# ESP32-S3-DevKit-C1.net
KiCad netlist of a schematic drawn in EasyEDA Pro
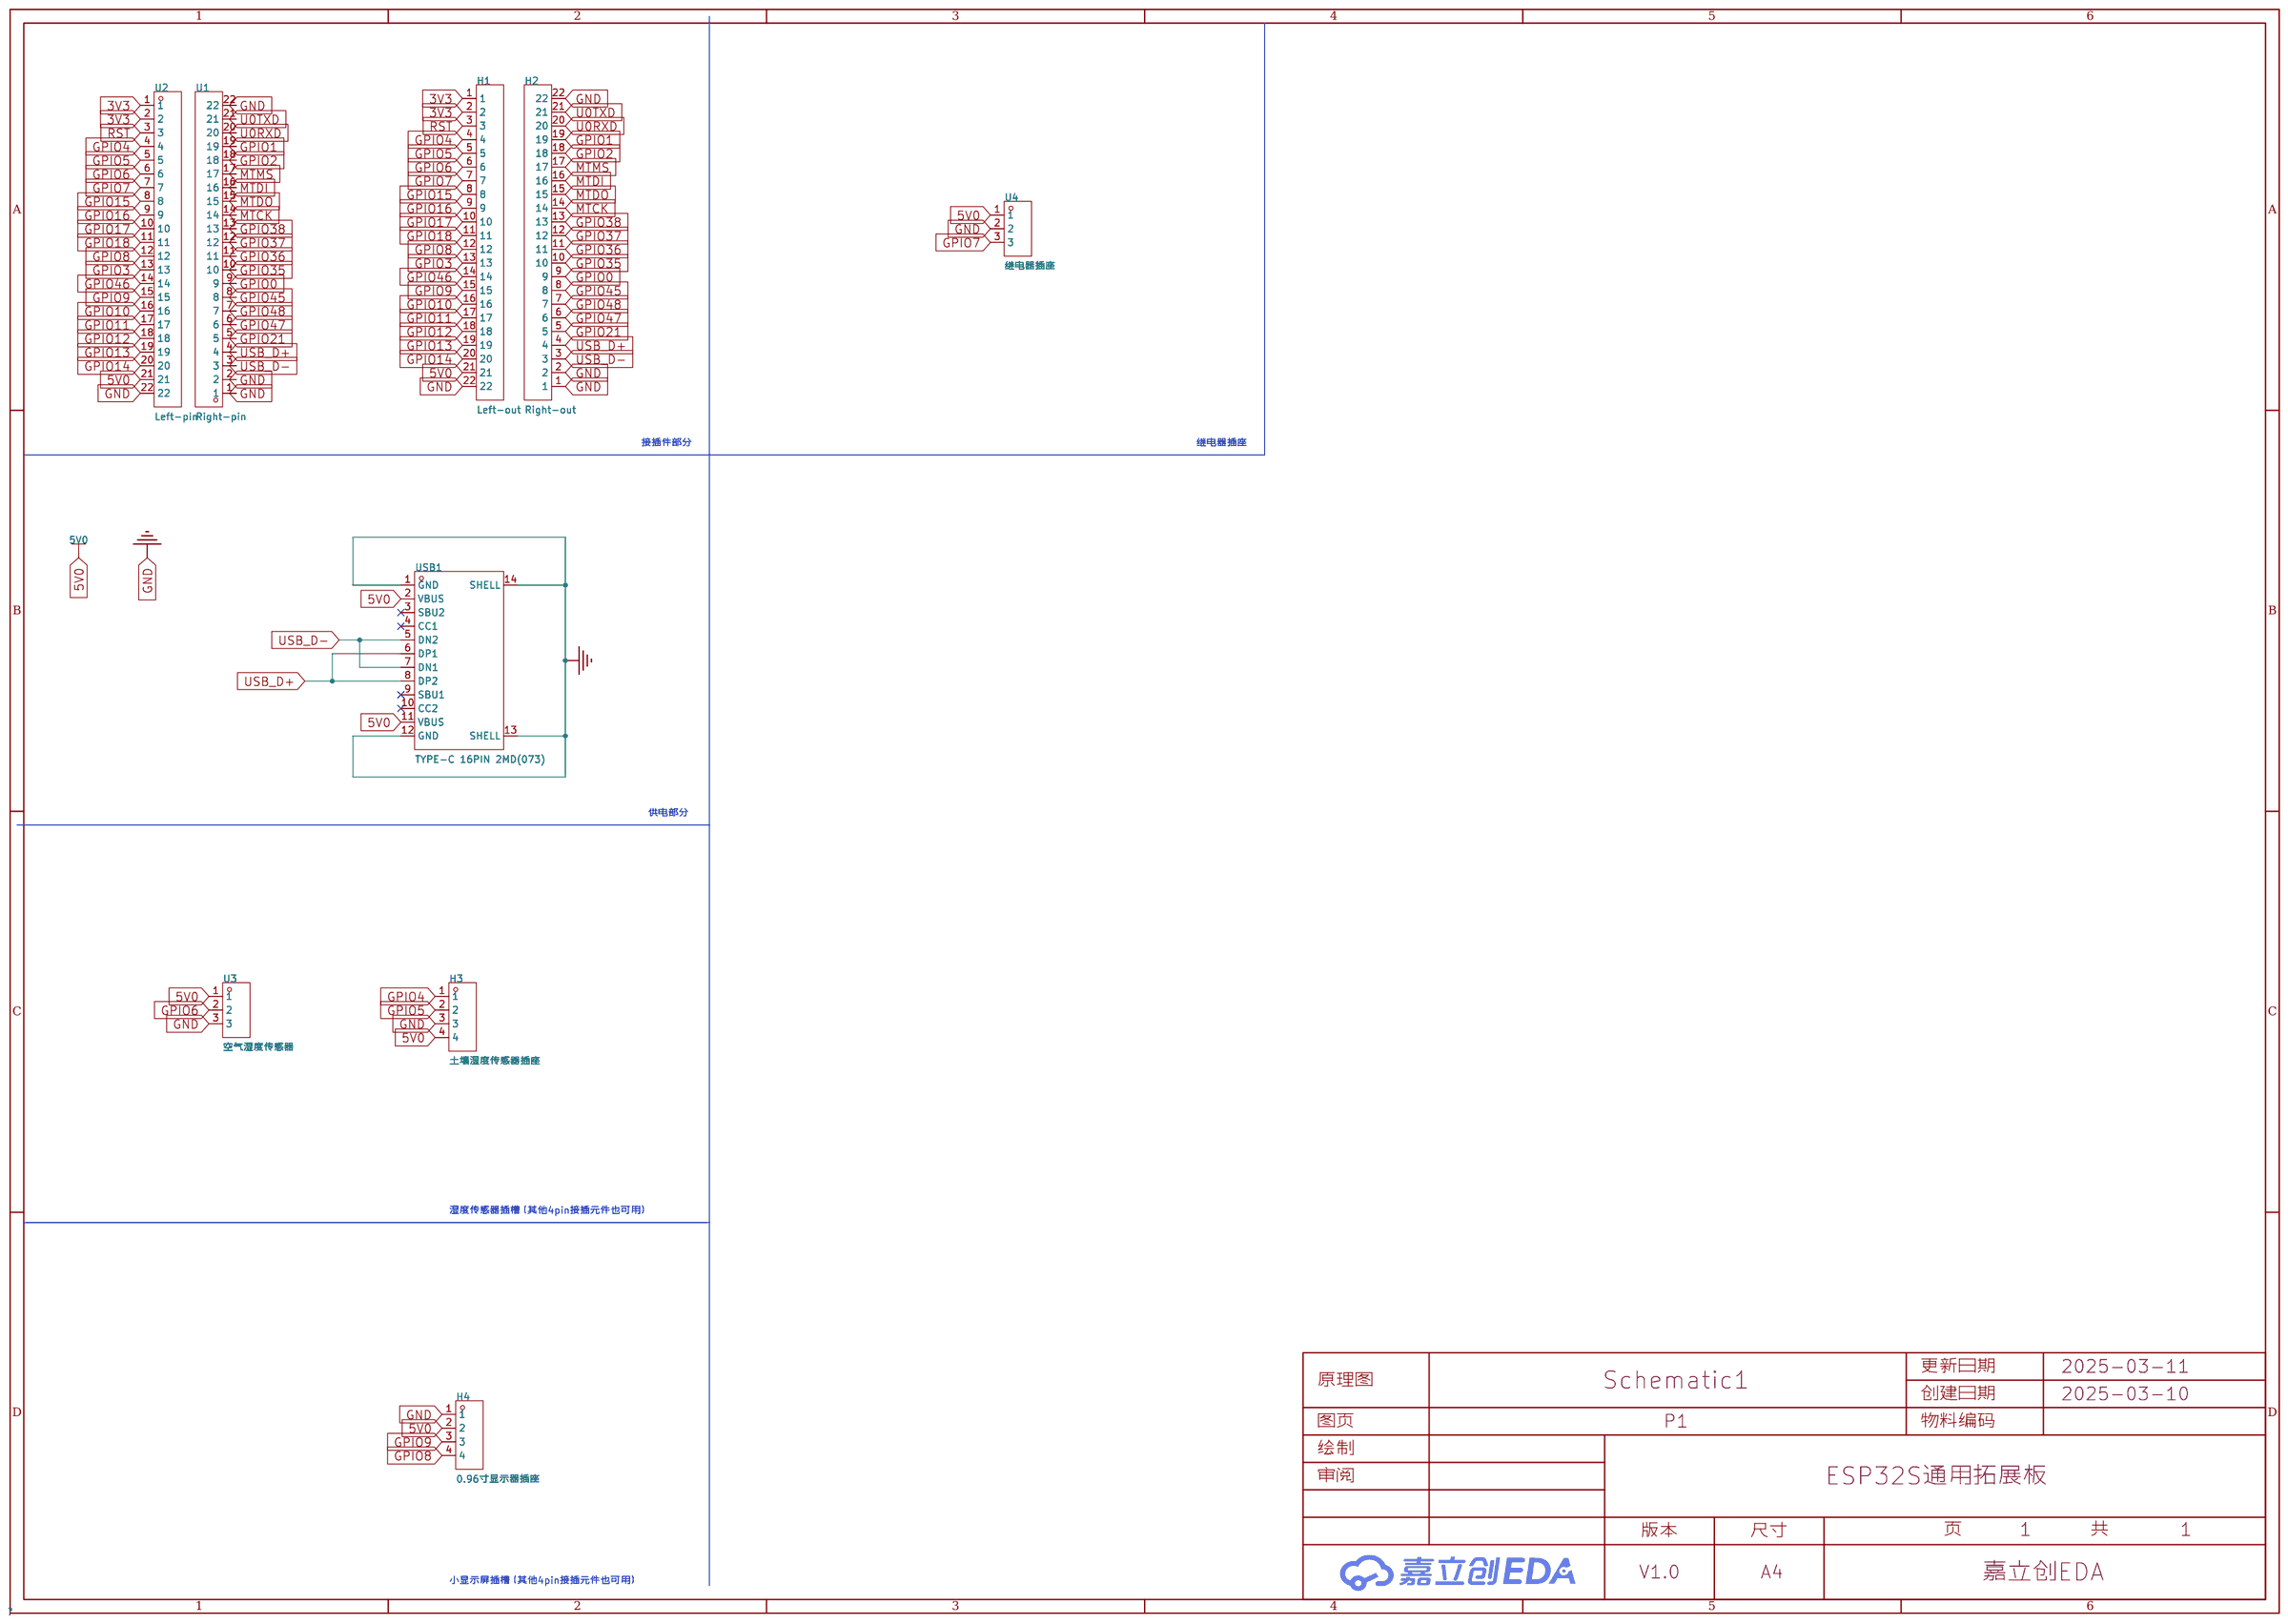
[diagram p0: schematic sheet]

(export (version "E")
  (design (tool "Eeschema 10.0.6"))
  (components
    (comp (ref "H1")
      (value "Left-out")
      (footprint "easyedapro:HDR-TH_22P-P2.54-V-M")
      (fields (field (name "Manufacturer") "XKB Connection(中国星坤)"))
      (libsource (lib "easyedapro") (part "X6511WV-22H-C30D60"))
    )
    (comp (ref "H2")
      (value "Right-out")
      (footprint "easyedapro:HDR-TH_22P-P2.54-V-M")
      (fields (field (name "Manufacturer") "XKB Connection(中国星坤)"))
      (libsource (lib "easyedapro") (part "X6511WV-22H-C30D60"))
    )
    (comp (ref "H3")
      (value "土壤湿度传感器插座")
      (footprint "easyedapro:HDR-TH_4P-P2.54-V-F")
      (fields (field (name "Manufacturer") "BOOMELE(博穆精密)"))
      (libsource (lib "easyedapro") (part "2.54-1*4P母"))
    )
    (comp (ref "H4")
      (value "0.96寸显示器插座")
      (footprint "easyedapro:HDR-TH_4P-P2.54-V-F")
      (fields (field (name "Manufacturer") "BOOMELE(博穆精密)"))
      (libsource (lib "easyedapro") (part "2.54-1*4P母"))
    )
    (comp (ref "U1")
      (value "Right-pin")
      (footprint "easyedapro:HDR-TH_22P-P2.54-V-F")
      (fields (field (name "Manufacturer") "Megastar(兆星)"))
      (libsource (lib "easyedapro") (part "ZX-PM2.54-1-22PY"))
    )
    (comp (ref "U2")
      (value "Left-pin")
      (footprint "easyedapro:HDR-TH_22P-P2.54-V-F")
      (fields (field (name "Manufacturer") "Megastar(兆星)"))
      (libsource (lib "easyedapro") (part "ZX-PM2.54-1-22PY"))
    )
    (comp (ref "U3")
      (value "空气湿度传感器")
      (footprint "easyedapro:HDR-TH_3P-P2.54_CS-1165SDIG")
      (libsource (lib "easyedapro") (part "排母2.54MM 1X3PIN"))
    )
    (comp (ref "U4")
      (value "继电器插座")
      (footprint "easyedapro:HDR-TH_3P-P2.54_CS-1165SDIG")
      (libsource (lib "easyedapro") (part "排母2.54MM 1X3PIN"))
    )
    (comp (ref "USB1")
      (value "TYPE-C 16PIN 2MD(073)")
      (footprint "easyedapro:USB-C-SMD_TYPE-C-6PIN-2MD-073")
      (description "连接器类型:Type-C;标准:USB 3.1;公母:母;安装方式:卧贴;触点数量:16P;端口数量:1;额定电流 - 电源:5A;工作温度范围:-25°C~+85°C;")
      (fields (field (name "Manufacturer") "SHOU HAN(首韩)"))
      (libsource (lib "easyedapro") (part "TYPE-C 16PIN 2MD(073)"))
    )
  )
  (nets
    (net (code "1") (name "3V3") (class "Default")
      (node (ref "H1") (pin "1") (pinfunction "1_1") (pintype "unspecified"))
      (node (ref "H1") (pin "2") (pinfunction "2_2") (pintype "unspecified"))
      (node (ref "U2") (pin "1") (pinfunction "1_1") (pintype "unspecified"))
      (node (ref "U2") (pin "2") (pinfunction "2_2") (pintype "unspecified"))
    )
    (net (code "2") (name "5V0") (class "Default")
      (node (ref "H1") (pin "21") (pinfunction "21_21") (pintype "unspecified"))
      (node (ref "H3") (pin "4") (pinfunction "4_4") (pintype "unspecified"))
      (node (ref "H4") (pin "2") (pinfunction "2_2") (pintype "unspecified"))
      (node (ref "U2") (pin "21") (pinfunction "21_21") (pintype "unspecified"))
      (node (ref "U3") (pin "1") (pinfunction "1_1") (pintype "unspecified"))
      (node (ref "U4") (pin "1") (pinfunction "1_1") (pintype "unspecified"))
      (node (ref "USB1") (pin "11") (pinfunction "VBUS_11") (pintype "unspecified"))
      (node (ref "USB1") (pin "2") (pinfunction "VBUS_2") (pintype "unspecified"))
    )
    (net (code "3") (name "GND") (class "Default")
      (node (ref "H1") (pin "22") (pinfunction "22_22") (pintype "unspecified"))
      (node (ref "H2") (pin "1") (pinfunction "1_1") (pintype "unspecified"))
      (node (ref "H2") (pin "2") (pinfunction "2_2") (pintype "unspecified"))
      (node (ref "H2") (pin "22") (pinfunction "22_22") (pintype "unspecified"))
      (node (ref "H3") (pin "3") (pinfunction "3_3") (pintype "unspecified"))
      (node (ref "H4") (pin "1") (pinfunction "1_1") (pintype "unspecified"))
      (node (ref "U1") (pin "1") (pinfunction "1_1") (pintype "unspecified"))
      (node (ref "U1") (pin "2") (pinfunction "2_2") (pintype "unspecified"))
      (node (ref "U1") (pin "22") (pinfunction "22_22") (pintype "unspecified"))
      (node (ref "U2") (pin "22") (pinfunction "22_22") (pintype "unspecified"))
      (node (ref "U3") (pin "3") (pinfunction "3_3") (pintype "unspecified"))
      (node (ref "U4") (pin "2") (pinfunction "2_2") (pintype "unspecified"))
      (node (ref "USB1") (pin "1") (pinfunction "GND_1") (pintype "unspecified"))
      (node (ref "USB1") (pin "12") (pinfunction "GND_12") (pintype "unspecified"))
      (node (ref "USB1") (pin "13") (pinfunction "SHELL_13") (pintype "unspecified"))
      (node (ref "USB1") (pin "14") (pinfunction "SHELL_14") (pintype "unspecified"))
    )
    (net (code "4") (name "GPIO0") (class "Default")
      (node (ref "H2") (pin "9") (pinfunction "9_9") (pintype "unspecified"))
      (node (ref "U1") (pin "9") (pinfunction "9_9") (pintype "unspecified"))
    )
    (net (code "5") (name "GPIO1") (class "Default")
      (node (ref "H2") (pin "19") (pinfunction "19_19") (pintype "unspecified"))
      (node (ref "U1") (pin "19") (pinfunction "19_19") (pintype "unspecified"))
    )
    (net (code "6") (name "GPIO2") (class "Default")
      (node (ref "H2") (pin "18") (pinfunction "18_18") (pintype "unspecified"))
      (node (ref "U1") (pin "18") (pinfunction "18_18") (pintype "unspecified"))
    )
    (net (code "7") (name "GPIO3") (class "Default")
      (node (ref "H1") (pin "13") (pinfunction "13_13") (pintype "unspecified"))
      (node (ref "U2") (pin "13") (pinfunction "13_13") (pintype "unspecified"))
    )
    (net (code "8") (name "GPIO4") (class "Default")
      (node (ref "H1") (pin "4") (pinfunction "4_4") (pintype "unspecified"))
      (node (ref "H3") (pin "1") (pinfunction "1_1") (pintype "unspecified"))
      (node (ref "U2") (pin "4") (pinfunction "4_4") (pintype "unspecified"))
    )
    (net (code "9") (name "GPIO5") (class "Default")
      (node (ref "H1") (pin "5") (pinfunction "5_5") (pintype "unspecified"))
      (node (ref "H3") (pin "2") (pinfunction "2_2") (pintype "unspecified"))
      (node (ref "U2") (pin "5") (pinfunction "5_5") (pintype "unspecified"))
    )
    (net (code "10") (name "GPIO6") (class "Default")
      (node (ref "H1") (pin "6") (pinfunction "6_6") (pintype "unspecified"))
      (node (ref "U2") (pin "6") (pinfunction "6_6") (pintype "unspecified"))
      (node (ref "U3") (pin "2") (pinfunction "2_2") (pintype "unspecified"))
    )
    (net (code "11") (name "GPIO7") (class "Default")
      (node (ref "H1") (pin "7") (pinfunction "7_7") (pintype "unspecified"))
      (node (ref "U2") (pin "7") (pinfunction "7_7") (pintype "unspecified"))
      (node (ref "U4") (pin "3") (pinfunction "3_3") (pintype "unspecified"))
    )
    (net (code "12") (name "GPIO8") (class "Default")
      (node (ref "H1") (pin "12") (pinfunction "12_12") (pintype "unspecified"))
      (node (ref "H4") (pin "4") (pinfunction "4_4") (pintype "unspecified"))
      (node (ref "U2") (pin "12") (pinfunction "12_12") (pintype "unspecified"))
    )
    (net (code "13") (name "GPIO9") (class "Default")
      (node (ref "H1") (pin "15") (pinfunction "15_15") (pintype "unspecified"))
      (node (ref "H4") (pin "3") (pinfunction "3_3") (pintype "unspecified"))
      (node (ref "U2") (pin "15") (pinfunction "15_15") (pintype "unspecified"))
    )
    (net (code "14") (name "GPIO10") (class "Default")
      (node (ref "H1") (pin "16") (pinfunction "16_16") (pintype "unspecified"))
      (node (ref "U2") (pin "16") (pinfunction "16_16") (pintype "unspecified"))
    )
    (net (code "15") (name "GPIO11") (class "Default")
      (node (ref "H1") (pin "17") (pinfunction "17_17") (pintype "unspecified"))
      (node (ref "U2") (pin "17") (pinfunction "17_17") (pintype "unspecified"))
    )
    (net (code "16") (name "GPIO12") (class "Default")
      (node (ref "H1") (pin "18") (pinfunction "18_18") (pintype "unspecified"))
      (node (ref "U2") (pin "18") (pinfunction "18_18") (pintype "unspecified"))
    )
    (net (code "17") (name "GPIO13") (class "Default")
      (node (ref "H1") (pin "19") (pinfunction "19_19") (pintype "unspecified"))
      (node (ref "U2") (pin "19") (pinfunction "19_19") (pintype "unspecified"))
    )
    (net (code "18") (name "GPIO14") (class "Default")
      (node (ref "H1") (pin "20") (pinfunction "20_20") (pintype "unspecified"))
      (node (ref "U2") (pin "20") (pinfunction "20_20") (pintype "unspecified"))
    )
    (net (code "19") (name "GPIO15") (class "Default")
      (node (ref "H1") (pin "8") (pinfunction "8_8") (pintype "unspecified"))
      (node (ref "U2") (pin "8") (pinfunction "8_8") (pintype "unspecified"))
    )
    (net (code "20") (name "GPIO16") (class "Default")
      (node (ref "H1") (pin "9") (pinfunction "9_9") (pintype "unspecified"))
      (node (ref "U2") (pin "9") (pinfunction "9_9") (pintype "unspecified"))
    )
    (net (code "21") (name "GPIO17") (class "Default")
      (node (ref "H1") (pin "10") (pinfunction "10_10") (pintype "unspecified"))
      (node (ref "U2") (pin "10") (pinfunction "10_10") (pintype "unspecified"))
    )
    (net (code "22") (name "GPIO18") (class "Default")
      (node (ref "H1") (pin "11") (pinfunction "11_11") (pintype "unspecified"))
      (node (ref "U2") (pin "11") (pinfunction "11_11") (pintype "unspecified"))
    )
    (net (code "23") (name "GPIO21") (class "Default")
      (node (ref "H2") (pin "5") (pinfunction "5_5") (pintype "unspecified"))
      (node (ref "U1") (pin "5") (pinfunction "5_5") (pintype "unspecified"))
    )
    (net (code "24") (name "GPIO35") (class "Default")
      (node (ref "H2") (pin "10") (pinfunction "10_10") (pintype "unspecified"))
      (node (ref "U1") (pin "10") (pinfunction "10_10") (pintype "unspecified"))
    )
    (net (code "25") (name "GPIO36") (class "Default")
      (node (ref "H2") (pin "11") (pinfunction "11_11") (pintype "unspecified"))
      (node (ref "U1") (pin "11") (pinfunction "11_11") (pintype "unspecified"))
    )
    (net (code "26") (name "GPIO37") (class "Default")
      (node (ref "H2") (pin "12") (pinfunction "12_12") (pintype "unspecified"))
      (node (ref "U1") (pin "12") (pinfunction "12_12") (pintype "unspecified"))
    )
    (net (code "27") (name "GPIO38") (class "Default")
      (node (ref "H2") (pin "13") (pinfunction "13_13") (pintype "unspecified"))
      (node (ref "U1") (pin "13") (pinfunction "13_13") (pintype "unspecified"))
    )
    (net (code "28") (name "GPIO45") (class "Default")
      (node (ref "H2") (pin "8") (pinfunction "8_8") (pintype "unspecified"))
      (node (ref "U1") (pin "8") (pinfunction "8_8") (pintype "unspecified"))
    )
    (net (code "29") (name "GPIO46") (class "Default")
      (node (ref "H1") (pin "14") (pinfunction "14_14") (pintype "unspecified"))
      (node (ref "U2") (pin "14") (pinfunction "14_14") (pintype "unspecified"))
    )
    (net (code "30") (name "GPIO47") (class "Default")
      (node (ref "H2") (pin "6") (pinfunction "6_6") (pintype "unspecified"))
      (node (ref "U1") (pin "6") (pinfunction "6_6") (pintype "unspecified"))
    )
    (net (code "31") (name "GPIO48") (class "Default")
      (node (ref "H2") (pin "7") (pinfunction "7_7") (pintype "unspecified"))
      (node (ref "U1") (pin "7") (pinfunction "7_7") (pintype "unspecified"))
    )
    (net (code "32") (name "MTCK") (class "Default")
      (node (ref "H2") (pin "14") (pinfunction "14_14") (pintype "unspecified"))
      (node (ref "U1") (pin "14") (pinfunction "14_14") (pintype "unspecified"))
    )
    (net (code "33") (name "MTDI") (class "Default")
      (node (ref "H2") (pin "16") (pinfunction "16_16") (pintype "unspecified"))
      (node (ref "U1") (pin "16") (pinfunction "16_16") (pintype "unspecified"))
    )
    (net (code "34") (name "MTDO") (class "Default")
      (node (ref "H2") (pin "15") (pinfunction "15_15") (pintype "unspecified"))
      (node (ref "U1") (pin "15") (pinfunction "15_15") (pintype "unspecified"))
    )
    (net (code "35") (name "MTMS") (class "Default")
      (node (ref "H2") (pin "17") (pinfunction "17_17") (pintype "unspecified"))
      (node (ref "U1") (pin "17") (pinfunction "17_17") (pintype "unspecified"))
    )
    (net (code "36") (name "RST") (class "Default")
      (node (ref "H1") (pin "3") (pinfunction "3_3") (pintype "unspecified"))
      (node (ref "U2") (pin "3") (pinfunction "3_3") (pintype "unspecified"))
    )
    (net (code "37") (name "U0RXD") (class "Default")
      (node (ref "H2") (pin "20") (pinfunction "20_20") (pintype "unspecified"))
      (node (ref "U1") (pin "20") (pinfunction "20_20") (pintype "unspecified"))
    )
    (net (code "38") (name "U0TXD") (class "Default")
      (node (ref "H2") (pin "21") (pinfunction "21_21") (pintype "unspecified"))
      (node (ref "U1") (pin "21") (pinfunction "21_21") (pintype "unspecified"))
    )
    (net (code "39") (name "USB_D+") (class "Default")
      (node (ref "H2") (pin "4") (pinfunction "4_4") (pintype "unspecified"))
      (node (ref "U1") (pin "4") (pinfunction "4_4") (pintype "unspecified"))
      (node (ref "USB1") (pin "6") (pinfunction "DP1_6") (pintype "unspecified"))
      (node (ref "USB1") (pin "8") (pinfunction "DP2_8") (pintype "unspecified"))
    )
    (net (code "40") (name "USB_D-") (class "Default")
      (node (ref "H2") (pin "3") (pinfunction "3_3") (pintype "unspecified"))
      (node (ref "U1") (pin "3") (pinfunction "3_3") (pintype "unspecified"))
      (node (ref "USB1") (pin "5") (pinfunction "DN2_5") (pintype "unspecified"))
      (node (ref "USB1") (pin "7") (pinfunction "DN1_7") (pintype "unspecified"))
    )
    (net (code "41") (name "unconnected-(USB1-CC1-Pad4)") (class "Default")
      (node (ref "USB1") (pin "4") (pinfunction "CC1_4") (pintype "unspecified+no_connect"))
    )
    (net (code "42") (name "unconnected-(USB1-CC2-Pad10)") (class "Default")
      (node (ref "USB1") (pin "10") (pinfunction "CC2_10") (pintype "unspecified+no_connect"))
    )
    (net (code "43") (name "unconnected-(USB1-SBU1-Pad9)") (class "Default")
      (node (ref "USB1") (pin "9") (pinfunction "SBU1_9") (pintype "unspecified+no_connect"))
    )
    (net (code "44") (name "unconnected-(USB1-SBU2-Pad3)") (class "Default")
      (node (ref "USB1") (pin "3") (pinfunction "SBU2_3") (pintype "unspecified+no_connect"))
    )
  )
)
